# ds1307_brkout.net
KiCad netlist of a schematic drawn in EAGLE
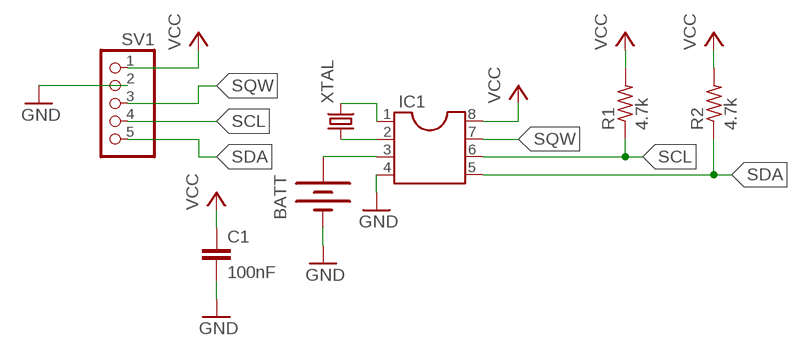
[diagram p0: schematic, sheet 1]

(export (version "E")
  (design (tool "Eeschema 10.0.6"))
  (components
    (comp (ref "BATT")
      (value "BATTERY20PTH")
      (footprint "eagle-import:BATTCOM_20MM_PTH")
      (libsource (lib "eagle-import") (part "BATTERY20PTH"))
    )
    (comp (ref "C1")
      (value "100nF")
      (footprint "eagle-import:C2.5-5")
      (libsource (lib "eagle-import") (part "C2.5/5"))
    )
    (comp (ref "IC1")
      (value "DIL8S")
      (footprint "eagle-import:SOCKET-08")
      (libsource (lib "eagle-import") (part "DIL8S"))
    )
    (comp (ref "R1")
      (value "4.7k")
      (footprint "eagle-import:0207_12")
      (libsource (lib "eagle-import") (part "R-US_0207/12"))
    )
    (comp (ref "R2")
      (value "4.7k")
      (footprint "eagle-import:0207_12")
      (libsource (lib "eagle-import") (part "R-US_0207/12"))
    )
    (comp (ref "SV1")
      (value "PINHD-1X5")
      (footprint "eagle-import:1X05")
      (libsource (lib "eagle-import") (part "PINHD-1X5"))
    )
    (comp (ref "XTAL")
      (value "CRYSTALTC26H")
      (footprint "eagle-import:TC26H")
      (libsource (lib "eagle-import") (part "CRYSTALTC26H"))
    )
  )
  (nets
    (net (code "1") (name "GND") (class "Default")
      (node (ref "BATT") (pin "2") (pinfunction "-_2") (pintype "power_in"))
      (node (ref "C1") (pin "2") (pinfunction "2_2") (pintype "passive"))
      (node (ref "IC1") (pin "4") (pinfunction "4_4") (pintype "passive"))
      (node (ref "SV1") (pin "2") (pinfunction "2_2") (pintype "passive"))
    )
    (net (code "2") (name "Net-(BATT-+)") (class "Default")
      (node (ref "BATT") (pin "1") (pinfunction "+_1") (pintype "power_in"))
      (node (ref "IC1") (pin "3") (pinfunction "3_3") (pintype "passive"))
    )
    (net (code "3") (name "Net-(IC1-Pad1)") (class "Default")
      (node (ref "IC1") (pin "1") (pinfunction "1_1") (pintype "passive"))
      (node (ref "XTAL") (pin "2") (pinfunction "2_2") (pintype "passive"))
    )
    (net (code "4") (name "Net-(IC1-Pad2)") (class "Default")
      (node (ref "IC1") (pin "2") (pinfunction "2_2") (pintype "passive"))
      (node (ref "XTAL") (pin "1") (pinfunction "1_1") (pintype "passive"))
    )
    (net (code "5") (name "SCL") (class "Default")
      (node (ref "IC1") (pin "6") (pinfunction "6_6") (pintype "passive"))
      (node (ref "R1") (pin "1") (pinfunction "1_1") (pintype "passive"))
      (node (ref "SV1") (pin "4") (pinfunction "4_4") (pintype "passive"))
    )
    (net (code "6") (name "SDA") (class "Default")
      (node (ref "IC1") (pin "5") (pinfunction "5_5") (pintype "passive"))
      (node (ref "R2") (pin "1") (pinfunction "1_1") (pintype "passive"))
      (node (ref "SV1") (pin "5") (pinfunction "5_5") (pintype "passive"))
    )
    (net (code "7") (name "SQW") (class "Default")
      (node (ref "IC1") (pin "7") (pinfunction "7_7") (pintype "passive"))
      (node (ref "SV1") (pin "3") (pinfunction "3_3") (pintype "passive"))
    )
    (net (code "8") (name "VCC") (class "Default")
      (node (ref "C1") (pin "1") (pinfunction "1_1") (pintype "passive"))
      (node (ref "IC1") (pin "8") (pinfunction "8_8") (pintype "passive"))
      (node (ref "R1") (pin "2") (pinfunction "2_2") (pintype "passive"))
      (node (ref "R2") (pin "2") (pinfunction "2_2") (pintype "passive"))
      (node (ref "SV1") (pin "1") (pinfunction "1_1") (pintype "passive"))
    )
  )
)
